# MCU_VoltageRegulator.net
KiCad netlist of a schematic drawn in Altium Designer
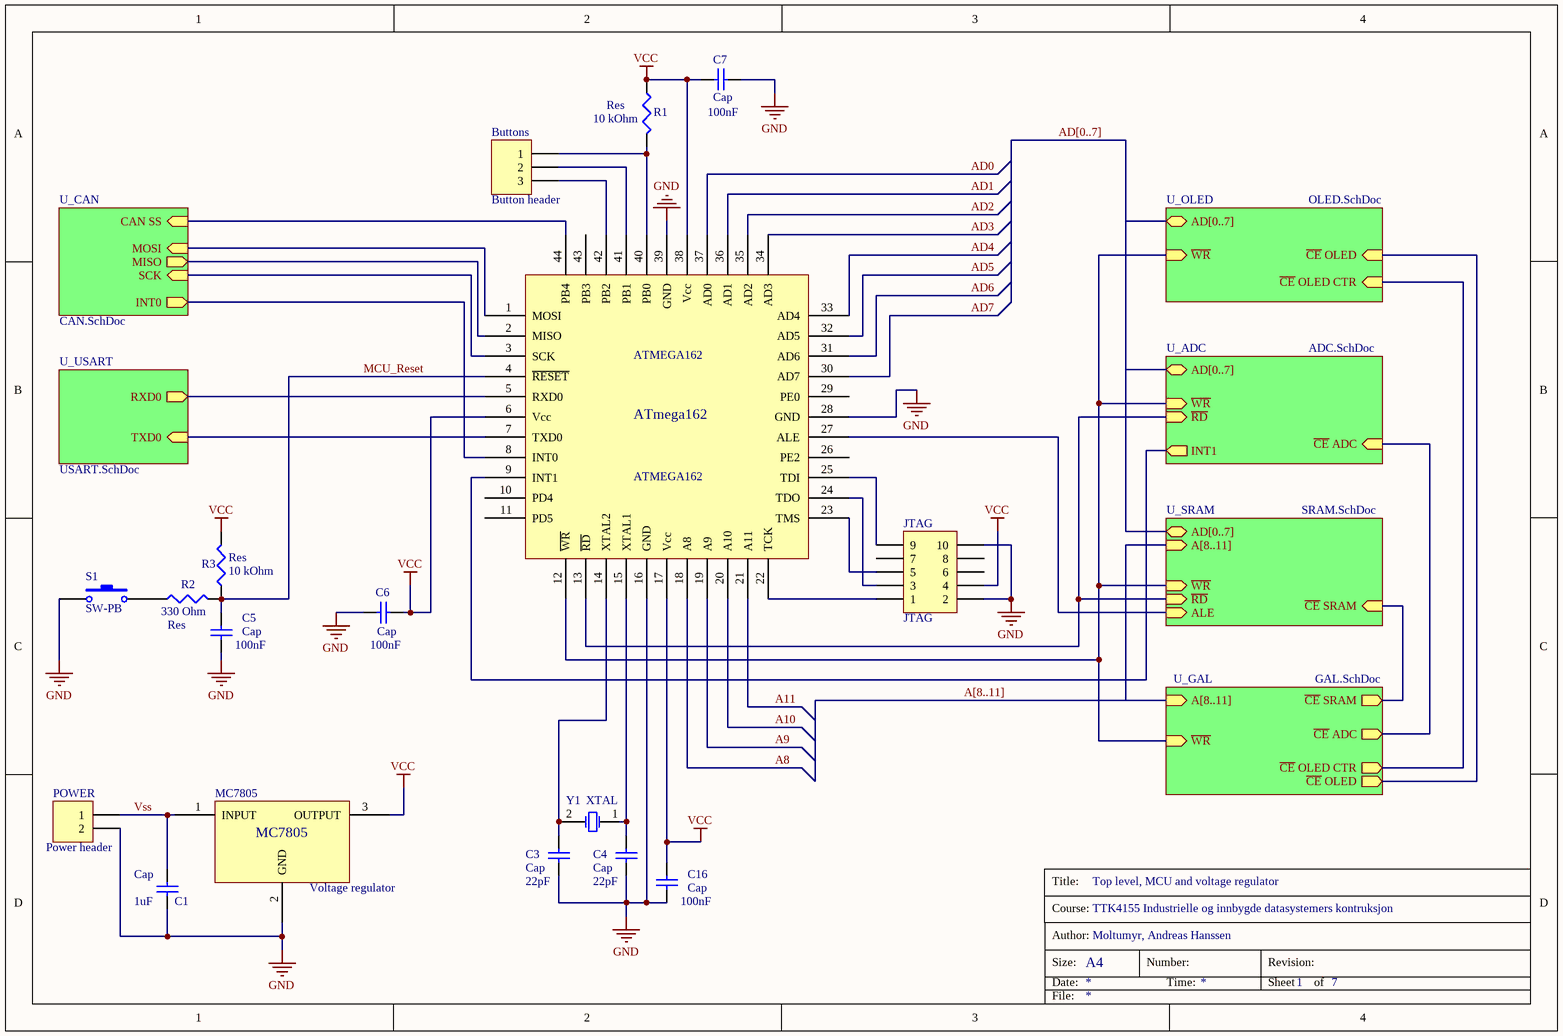
[diagram p0: MCU&VoltageRegulator.SchDoc]

(export (version "E")
  (design (tool "Eeschema 10.0.6"))
  (components
    (comp (ref "ATMEGA162")
      (value "ATMEGA162")
      (footprint "ATmega162 TQFP 44-pin")
      (description "Atmega162 MicroControllerUnit")
      (libsource (lib "IIDKLib") (part "ATMEGA162"))
    )
    (comp (ref "Buttons")
      (value "Button header")
      (footprint "HDR1X3")
      (description "Header, 3-Pin")
      (fields (field (name "PUBLISHER") "Altium Limited"))
      (libsource (lib "Miscellaneous Connectors") (part "Header 3"))
    )
    (comp (ref "C1")
      (value "Cap")
      (footprint "C1210")
      (description "Capacitor (Semiconductor SIM Model)")
      (fields (field (name "ALTIUM_VALUE") "1uF") (field (name "PUBLISHER") "Altium Limited"))
      (libsource (lib "Miscellaneous Devices") (part "Cap Semi"))
    )
    (comp (ref "C3")
      (value "Cap")
      (footprint "C1210")
      (description "Capacitor (Semiconductor SIM Model)")
      (fields (field (name "ALTIUM_VALUE") "22pF") (field (name "PUBLISHER") "Altium Limited"))
      (libsource (lib "Miscellaneous Devices") (part "Cap Semi"))
    )
    (comp (ref "C4")
      (value "Cap")
      (footprint "C1210")
      (description "Capacitor (Semiconductor SIM Model)")
      (fields (field (name "ALTIUM_VALUE") "22pF") (field (name "PUBLISHER") "Altium Limited"))
      (libsource (lib "Miscellaneous Devices") (part "Cap Semi"))
    )
    (comp (ref "C5")
      (value "Cap")
      (footprint "C1210")
      (description "Capacitor (Semiconductor SIM Model)")
      (fields (field (name "ALTIUM_VALUE") "100nF") (field (name "PUBLISHER") "Altium Limited"))
      (libsource (lib "Miscellaneous Devices") (part "Cap Semi"))
    )
    (comp (ref "C6")
      (value "Cap")
      (footprint "C1210")
      (description "Capacitor (Semiconductor SIM Model)")
      (fields (field (name "ALTIUM_VALUE") "100nF") (field (name "PUBLISHER") "Altium Limited"))
      (libsource (lib "Miscellaneous Devices") (part "Cap Semi"))
    )
    (comp (ref "C7")
      (value "Cap")
      (footprint "C1210")
      (description "Capacitor (Semiconductor SIM Model)")
      (fields (field (name "ALTIUM_VALUE") "100nF") (field (name "PUBLISHER") "Altium Limited"))
      (libsource (lib "Miscellaneous Devices") (part "Cap Semi"))
    )
    (comp (ref "C16")
      (value "Cap")
      (footprint "C1210")
      (description "Capacitor (Semiconductor SIM Model)")
      (fields (field (name "ALTIUM_VALUE") "100nF") (field (name "PUBLISHER") "Altium Limited"))
      (libsource (lib "Miscellaneous Devices") (part "Cap Semi"))
    )
    (comp (ref "JTAG")
      (value "JTAG")
      (footprint "HDR2X5")
      (description "Header, 5-Pin, Dual row")
      (fields (field (name "PUBLISHER") "Altium Limited"))
      (libsource (lib "Miscellaneous Connectors") (part "Header 5X2"))
    )
    (comp (ref "MC7805")
      (value "Voltage regulator")
      (footprint "IIDKLib:MC7805 DPAK 3-PIN")
      (description "MC7805 Voltage Regulator")
      (libsource (lib "IIDKLib") (part "MC7805"))
    )
    (comp (ref "POWER")
      (value "Power header")
      (footprint "HDR1X2")
      (description "Header, 2-Pin")
      (fields (field (name "PUBLISHER") "Altium Limited"))
      (libsource (lib "Miscellaneous Connectors") (part "Header 2"))
    )
    (comp (ref "R1")
      (value "Res")
      (footprint "14-1210")
      (description "Resistor")
      (fields (field (name "ALTIUM_VALUE") "10 kOhm") (field (name "PUBLISHER") "Altium Limited"))
      (libsource (lib "Miscellaneous Devices") (part "Res3"))
    )
    (comp (ref "R2")
      (value "Res")
      (footprint "14-1210")
      (description "Resistor")
      (fields (field (name "ALTIUM_VALUE") "330 Ohm") (field (name "PUBLISHER") "Altium Limited"))
      (libsource (lib "Miscellaneous Devices") (part "Res3"))
    )
    (comp (ref "R3")
      (value "Res")
      (footprint "14-1210")
      (description "Resistor")
      (fields (field (name "ALTIUM_VALUE") "10 kOhm") (field (name "PUBLISHER") "Altium Limited"))
      (libsource (lib "Miscellaneous Devices") (part "Res3"))
    )
    (comp (ref "S1")
      (value "SW-PB")
      (footprint "SPST-2")
      (description "Switch")
      (fields (field (name "PUBLISHER") "Altium Limited"))
      (libsource (lib "Miscellaneous Devices") (part "SW-PB"))
    )
    (comp (ref "Y1")
      (value "XTAL")
      (footprint "R38")
      (description "Crystal Oscillator")
      (fields (field (name "PUBLISHER") "Altium Limited"))
      (libsource (lib "Miscellaneous Devices") (part "XTAL"))
    )
  )
  (nets
    (net (code "1") (name "/A8") (class "Default")
      (node (ref "ATMEGA162") (pin "18") (pinfunction "A8_18") (pintype "passive"))
    )
    (net (code "2") (name "/A9") (class "Default")
      (node (ref "ATMEGA162") (pin "19") (pinfunction "A9_19") (pintype "passive"))
    )
    (net (code "3") (name "/A10") (class "Default")
      (node (ref "ATMEGA162") (pin "20") (pinfunction "A10_20") (pintype "passive"))
    )
    (net (code "4") (name "/A11") (class "Default")
      (node (ref "ATMEGA162") (pin "21") (pinfunction "A11_21") (pintype "passive"))
    )
    (net (code "5") (name "/AD0") (class "Default")
      (node (ref "ATMEGA162") (pin "37") (pinfunction "AD0_37") (pintype "passive"))
    )
    (net (code "6") (name "/AD1") (class "Default")
      (node (ref "ATMEGA162") (pin "36") (pinfunction "AD1_36") (pintype "passive"))
    )
    (net (code "7") (name "/AD2") (class "Default")
      (node (ref "ATMEGA162") (pin "35") (pinfunction "AD2_35") (pintype "passive"))
    )
    (net (code "8") (name "/AD3") (class "Default")
      (node (ref "ATMEGA162") (pin "34") (pinfunction "AD3_34") (pintype "passive"))
    )
    (net (code "9") (name "/AD4") (class "Default")
      (node (ref "ATMEGA162") (pin "33") (pinfunction "AD4_33") (pintype "passive"))
    )
    (net (code "10") (name "/AD5") (class "Default")
      (node (ref "ATMEGA162") (pin "32") (pinfunction "AD5_32") (pintype "passive"))
    )
    (net (code "11") (name "/AD6") (class "Default")
      (node (ref "ATMEGA162") (pin "31") (pinfunction "AD6_31") (pintype "passive"))
    )
    (net (code "12") (name "/AD7") (class "Default")
      (node (ref "ATMEGA162") (pin "30") (pinfunction "AD7_30") (pintype "passive"))
    )
    (net (code "14") (name "/ALE") (class "Default")
      (node (ref "ATMEGA162") (pin "27") (pinfunction "ALE_27") (pintype "passive"))
    )
    (net (code "16") (name "/CAN SS") (class "Default")
      (node (ref "ATMEGA162") (pin "44") (pinfunction "PB4_44") (pintype "passive"))
    )
    (net (code "17") (name "/INT0") (class "Default")
      (node (ref "ATMEGA162") (pin "8") (pinfunction "INT0_8") (pintype "passive"))
    )
    (net (code "18") (name "/INT1") (class "Default")
      (node (ref "ATMEGA162") (pin "9") (pinfunction "INT1_9") (pintype "passive"))
    )
    (net (code "19") (name "/MCU_Reset") (class "Default")
      (node (ref "ATMEGA162") (pin "4") (pinfunction "~{RESET}_4") (pintype "passive"))
      (node (ref "C5") (pin "2") (pinfunction "2_2") (pintype "passive"))
      (node (ref "R2") (pin "2") (pinfunction "2_2") (pintype "passive"))
      (node (ref "R3") (pin "1") (pinfunction "1_1") (pintype "passive"))
    )
    (net (code "20") (name "/MISO") (class "Default")
      (node (ref "ATMEGA162") (pin "2") (pinfunction "MISO_2") (pintype "passive"))
    )
    (net (code "21") (name "/MOSI") (class "Default")
      (node (ref "ATMEGA162") (pin "1") (pinfunction "MOSI_1") (pintype "passive"))
    )
    (net (code "22") (name "/RXD0") (class "Default")
      (node (ref "ATMEGA162") (pin "5") (pinfunction "RXD0_5") (pintype "passive"))
    )
    (net (code "23") (name "/SCK") (class "Default")
      (node (ref "ATMEGA162") (pin "3") (pinfunction "SCK_3") (pintype "passive"))
    )
    (net (code "24") (name "/TXD0") (class "Default")
      (node (ref "ATMEGA162") (pin "7") (pinfunction "TXD0_7") (pintype "passive"))
    )
    (net (code "25") (name "/Vss") (class "Default")
      (node (ref "C1") (pin "2") (pinfunction "2_2") (pintype "passive"))
      (node (ref "MC7805") (pin "1") (pinfunction "INPUT_1") (pintype "passive"))
      (node (ref "POWER") (pin "1") (pinfunction "1_1") (pintype "passive"))
    )
    (net (code "30") (name "/~{RD}") (class "Default")
      (node (ref "ATMEGA162") (pin "13") (pinfunction "~{RD}_13") (pintype "passive"))
    )
    (net (code "31") (name "/~{WR}") (class "Default")
      (node (ref "ATMEGA162") (pin "12") (pinfunction "~{WR}_12") (pintype "passive"))
    )
    (net (code "32") (name "GND") (class "Default")
      (node (ref "ATMEGA162") (pin "16") (pinfunction "GND_16") (pintype "passive"))
      (node (ref "ATMEGA162") (pin "28") (pinfunction "GND_28") (pintype "passive"))
      (node (ref "ATMEGA162") (pin "39") (pinfunction "GND_39") (pintype "passive"))
      (node (ref "C1") (pin "1") (pinfunction "1_1") (pintype "passive"))
      (node (ref "C16") (pin "2") (pinfunction "2_2") (pintype "passive"))
      (node (ref "C3") (pin "2") (pinfunction "2_2") (pintype "passive"))
      (node (ref "C4") (pin "1") (pinfunction "1_1") (pintype "passive"))
      (node (ref "C5") (pin "1") (pinfunction "1_1") (pintype "passive"))
      (node (ref "C6") (pin "2") (pinfunction "2_2") (pintype "passive"))
      (node (ref "C7") (pin "2") (pinfunction "2_2") (pintype "passive"))
      (node (ref "JTAG") (pin "10") (pinfunction "10_10") (pintype "passive"))
      (node (ref "JTAG") (pin "2") (pinfunction "2_2") (pintype "passive"))
      (node (ref "MC7805") (pin "2") (pinfunction "GND_2") (pintype "passive"))
      (node (ref "POWER") (pin "2") (pinfunction "2_2") (pintype "passive"))
      (node (ref "S1") (pin "1") (pinfunction "1_1") (pintype "passive"))
    )
    (net (code "33") (name "Net-(ATMEGA162-PB0)") (class "Default")
      (node (ref "ATMEGA162") (pin "40") (pinfunction "PB0_40") (pintype "passive"))
      (node (ref "Buttons") (pin "1") (pinfunction "1_1") (pintype "passive"))
      (node (ref "R1") (pin "2") (pinfunction "2_2") (pintype "passive"))
    )
    (net (code "34") (name "Net-(ATMEGA162-PB1)") (class "Default")
      (node (ref "ATMEGA162") (pin "41") (pinfunction "PB1_41") (pintype "passive"))
      (node (ref "Buttons") (pin "2") (pinfunction "2_2") (pintype "passive"))
    )
    (net (code "35") (name "Net-(ATMEGA162-PB2)") (class "Default")
      (node (ref "ATMEGA162") (pin "42") (pinfunction "PB2_42") (pintype "passive"))
      (node (ref "Buttons") (pin "3") (pinfunction "3_3") (pintype "passive"))
    )
    (net (code "36") (name "Net-(ATMEGA162-TCK)") (class "Default")
      (node (ref "ATMEGA162") (pin "22") (pinfunction "TCK_22") (pintype "passive"))
      (node (ref "JTAG") (pin "1") (pinfunction "1_1") (pintype "passive"))
    )
    (net (code "37") (name "Net-(ATMEGA162-TDI)") (class "Default")
      (node (ref "ATMEGA162") (pin "25") (pinfunction "TDI_25") (pintype "passive"))
      (node (ref "JTAG") (pin "9") (pinfunction "9_9") (pintype "passive"))
    )
    (net (code "38") (name "Net-(ATMEGA162-TDO)") (class "Default")
      (node (ref "ATMEGA162") (pin "24") (pinfunction "TDO_24") (pintype "passive"))
      (node (ref "JTAG") (pin "3") (pinfunction "3_3") (pintype "passive"))
    )
    (net (code "39") (name "Net-(ATMEGA162-TMS)") (class "Default")
      (node (ref "ATMEGA162") (pin "23") (pinfunction "TMS_23") (pintype "passive"))
      (node (ref "JTAG") (pin "5") (pinfunction "5_5") (pintype "passive"))
    )
    (net (code "40") (name "Net-(ATMEGA162-XTAL1)") (class "Default")
      (node (ref "ATMEGA162") (pin "15") (pinfunction "XTAL1_15") (pintype "passive"))
      (node (ref "C4") (pin "2") (pinfunction "2_2") (pintype "passive"))
      (node (ref "Y1") (pin "1") (pinfunction "OSC1_1") (pintype "passive"))
    )
    (net (code "41") (name "Net-(ATMEGA162-XTAL2)") (class "Default")
      (node (ref "ATMEGA162") (pin "14") (pinfunction "XTAL2_14") (pintype "passive"))
      (node (ref "C3") (pin "1") (pinfunction "1_1") (pintype "passive"))
      (node (ref "Y1") (pin "2") (pinfunction "OSC2_2") (pintype "passive"))
    )
    (net (code "42") (name "Net-(R2-Pad1)") (class "Default")
      (node (ref "R2") (pin "1") (pinfunction "1_1") (pintype "passive"))
      (node (ref "S1") (pin "2") (pinfunction "2_2") (pintype "passive"))
    )
    (net (code "43") (name "VCC") (class "Default")
      (node (ref "ATMEGA162") (pin "17") (pinfunction "Vcc_17") (pintype "passive"))
      (node (ref "ATMEGA162") (pin "38") (pinfunction "Vcc_38") (pintype "passive"))
      (node (ref "ATMEGA162") (pin "6") (pinfunction "Vcc_6") (pintype "passive"))
      (node (ref "C16") (pin "1") (pinfunction "1_1") (pintype "passive"))
      (node (ref "C6") (pin "1") (pinfunction "1_1") (pintype "passive"))
      (node (ref "C7") (pin "1") (pinfunction "1_1") (pintype "passive"))
      (node (ref "JTAG") (pin "4") (pinfunction "4_4") (pintype "passive"))
      (node (ref "MC7805") (pin "3") (pinfunction "OUTPUT_3") (pintype "passive"))
      (node (ref "R1") (pin "1") (pinfunction "1_1") (pintype "passive"))
      (node (ref "R3") (pin "2") (pinfunction "2_2") (pintype "passive"))
    )
    (net (code "44") (name "unconnected-(ATMEGA162-PB3-Pad43)") (class "Default")
      (node (ref "ATMEGA162") (pin "43") (pinfunction "PB3_43") (pintype "passive"))
    )
    (net (code "45") (name "unconnected-(ATMEGA162-PD4-Pad10)") (class "Default")
      (node (ref "ATMEGA162") (pin "10") (pinfunction "PD4_10") (pintype "passive"))
    )
    (net (code "46") (name "unconnected-(ATMEGA162-PD5-Pad11)") (class "Default")
      (node (ref "ATMEGA162") (pin "11") (pinfunction "PD5_11") (pintype "passive"))
    )
    (net (code "47") (name "unconnected-(ATMEGA162-PE0-Pad29)") (class "Default")
      (node (ref "ATMEGA162") (pin "29") (pinfunction "PE0_29") (pintype "passive"))
    )
    (net (code "48") (name "unconnected-(ATMEGA162-PE2-Pad26)") (class "Default")
      (node (ref "ATMEGA162") (pin "26") (pinfunction "PE2_26") (pintype "passive"))
    )
    (net (code "49") (name "unconnected-(JTAG-Pad6)") (class "Default")
      (node (ref "JTAG") (pin "6") (pinfunction "6_6") (pintype "passive"))
    )
    (net (code "50") (name "unconnected-(JTAG-Pad7)") (class "Default")
      (node (ref "JTAG") (pin "7") (pinfunction "7_7") (pintype "passive"))
    )
    (net (code "51") (name "unconnected-(JTAG-Pad8)") (class "Default")
      (node (ref "JTAG") (pin "8") (pinfunction "8_8") (pintype "passive"))
    )
  )
)
